# schematic.net
KiCad netlist of a schematic drawn in EAGLE
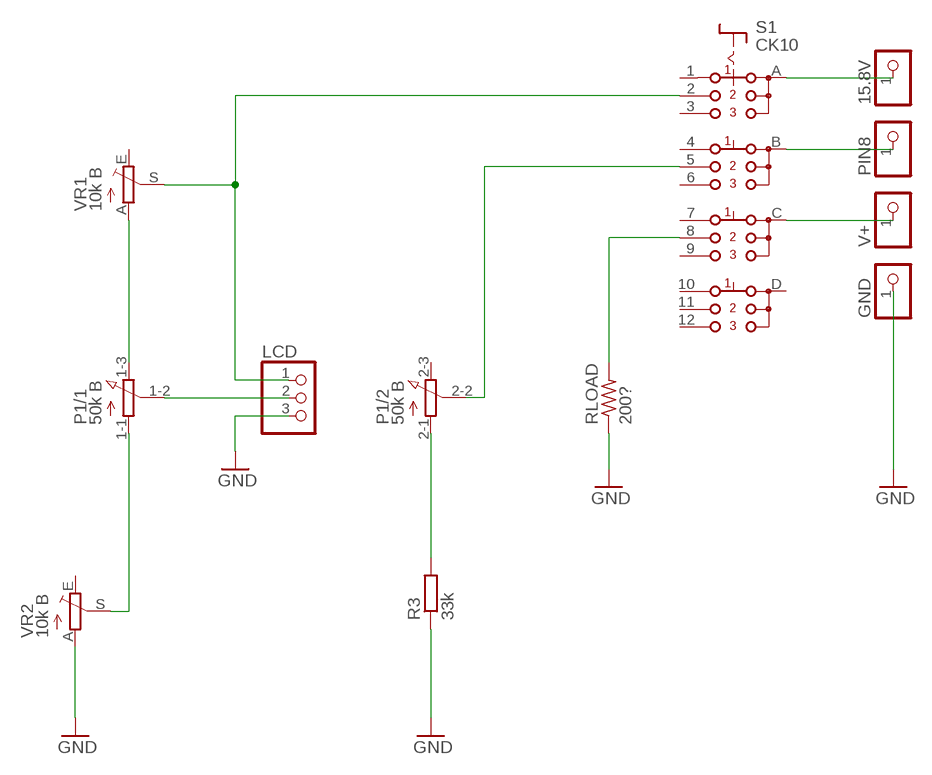
[diagram p0: schematic, sheet 1]

(export (version "E")
  (design (tool "Eeschema 10.0.6"))
  (components
    (comp (ref "15.8V")
      (value "PINHD-1X1")
      (footprint "eagle-import:1X01")
      (libsource (lib "eagle-import") (part "PINHD-1X1"))
    )
    (comp (ref "GND")
      (value "PINHD-1X1")
      (footprint "eagle-import:1X01")
      (libsource (lib "eagle-import") (part "PINHD-1X1"))
    )
    (comp (ref "LCD")
      (value "PINHD-1X3")
      (footprint "eagle-import:1X03")
      (libsource (lib "eagle-import") (part "PINHD-1X3"))
    )
    (comp (ref "P1")
      (value "50k B")
      (footprint "eagle-import:3RP_1610G")
      (libsource (lib "eagle-import") (part "3RP/1610G"))
    )
    (comp (ref "PIN8")
      (value "PINHD-1X1")
      (footprint "eagle-import:1X01")
      (libsource (lib "eagle-import") (part "PINHD-1X1"))
    )
    (comp (ref "R3")
      (value "33k")
      (footprint "eagle-import:0204_5")
      (libsource (lib "eagle-import") (part "R-EU_0204/5"))
    )
    (comp (ref "RLOAD")
      (value "200?")
      (footprint "eagle-import:VTA52")
      (libsource (lib "eagle-import") (part "R-US_VTA52"))
    )
    (comp (ref "S1")
      (value "CK10")
      (footprint "eagle-import:CK10")
      (libsource (lib "eagle-import") (part "CK10"))
    )
    (comp (ref "V+")
      (value "PINHD-1X1")
      (footprint "eagle-import:1X01")
      (libsource (lib "eagle-import") (part "PINHD-1X1"))
    )
    (comp (ref "VR1")
      (value "10k B")
      (footprint "eagle-import:RJ9W")
      (libsource (lib "eagle-import") (part "TRIM_EU-RJ9W"))
    )
    (comp (ref "VR2")
      (value "10k B")
      (footprint "eagle-import:RJ9W")
      (libsource (lib "eagle-import") (part "TRIM_EU-RJ9W"))
    )
  )
  (nets
    (net (code "1") (name "GND") (class "Default")
      (node (ref "GND") (pin "1") (pinfunction "1_1") (pintype "passive"))
      (node (ref "LCD") (pin "3") (pinfunction "3_3") (pintype "passive"))
      (node (ref "R3") (pin "1") (pinfunction "1_1") (pintype "passive"))
      (node (ref "RLOAD") (pin "1") (pinfunction "1_1") (pintype "passive"))
      (node (ref "VR2") (pin "A") (pinfunction "A_A") (pintype "passive"))
    )
    (net (code "2") (name "Net-(15.8V-Pad1)") (class "Default")
      (node (ref "15.8V") (pin "1") (pinfunction "1_1") (pintype "passive"))
      (node (ref "S1") (pin "A") (pinfunction "A_A") (pintype "passive"))
    )
    (net (code "3") (name "Net-(P1A-A)") (class "Default")
      (node (ref "P1") (pin "1-1") (pinfunction "A_1-1") (pintype "passive"))
      (node (ref "VR2") (pin "S") (pinfunction "S_S") (pintype "passive"))
    )
    (net (code "4") (name "Net-(P1A-E)") (class "Default")
      (node (ref "P1") (pin "1-3") (pinfunction "E_1-3") (pintype "passive"))
      (node (ref "VR1") (pin "A") (pinfunction "A_A") (pintype "passive"))
    )
    (net (code "5") (name "Net-(P1A-S)") (class "Default")
      (node (ref "LCD") (pin "2") (pinfunction "2_2") (pintype "passive"))
      (node (ref "P1") (pin "1-2") (pinfunction "S_1-2") (pintype "passive"))
    )
    (net (code "6") (name "Net-(P1B-A)") (class "Default")
      (node (ref "P1") (pin "2-1") (pinfunction "A_2-1") (pintype "passive"))
      (node (ref "R3") (pin "2") (pinfunction "2_2") (pintype "passive"))
    )
    (net (code "7") (name "Net-(P1B-S)") (class "Default")
      (node (ref "P1") (pin "2-2") (pinfunction "S_2-2") (pintype "passive"))
      (node (ref "S1") (pin "5") (pinfunction "B2_5") (pintype "passive"))
    )
    (net (code "8") (name "Net-(PIN8-Pad1)") (class "Default")
      (node (ref "PIN8") (pin "1") (pinfunction "1_1") (pintype "passive"))
      (node (ref "S1") (pin "B") (pinfunction "B_B") (pintype "passive"))
    )
    (net (code "9") (name "Net-(S1-A2)") (class "Default")
      (node (ref "LCD") (pin "1") (pinfunction "1_1") (pintype "passive"))
      (node (ref "S1") (pin "2") (pinfunction "A2_2") (pintype "passive"))
      (node (ref "VR1") (pin "S") (pinfunction "S_S") (pintype "passive"))
    )
    (net (code "10") (name "Net-(S1-C2)") (class "Default")
      (node (ref "RLOAD") (pin "2") (pinfunction "2_2") (pintype "passive"))
      (node (ref "S1") (pin "8") (pinfunction "C2_8") (pintype "passive"))
    )
    (net (code "11") (name "Net-(S1-PadC)") (class "Default")
      (node (ref "S1") (pin "C") (pinfunction "C_C") (pintype "passive"))
      (node (ref "V+") (pin "1") (pinfunction "1_1") (pintype "passive"))
    )
    (net (code "12") (name "unconnected-(P1B-E-Pad2-3)") (class "Default")
      (node (ref "P1") (pin "2-3") (pinfunction "E_2-3") (pintype "passive"))
    )
    (net (code "13") (name "unconnected-(S1-A1-Pad1)") (class "Default")
      (node (ref "S1") (pin "1") (pinfunction "A1_1") (pintype "passive"))
    )
    (net (code "14") (name "unconnected-(S1-A3-Pad3)") (class "Default")
      (node (ref "S1") (pin "3") (pinfunction "A3_3") (pintype "passive"))
    )
    (net (code "15") (name "unconnected-(S1-B1-Pad4)") (class "Default")
      (node (ref "S1") (pin "4") (pinfunction "B1_4") (pintype "passive"))
    )
    (net (code "16") (name "unconnected-(S1-B3-Pad6)") (class "Default")
      (node (ref "S1") (pin "6") (pinfunction "B3_6") (pintype "passive"))
    )
    (net (code "17") (name "unconnected-(S1-C1-Pad7)") (class "Default")
      (node (ref "S1") (pin "7") (pinfunction "C1_7") (pintype "passive"))
    )
    (net (code "18") (name "unconnected-(S1-C3-Pad9)") (class "Default")
      (node (ref "S1") (pin "9") (pinfunction "C3_9") (pintype "passive"))
    )
    (net (code "19") (name "unconnected-(S1-D1-Pad10)") (class "Default")
      (node (ref "S1") (pin "10") (pinfunction "D1_10") (pintype "passive"))
    )
    (net (code "20") (name "unconnected-(S1-D2-Pad11)") (class "Default")
      (node (ref "S1") (pin "11") (pinfunction "D2_11") (pintype "passive"))
    )
    (net (code "21") (name "unconnected-(S1-D3-Pad12)") (class "Default")
      (node (ref "S1") (pin "12") (pinfunction "D3_12") (pintype "passive"))
    )
    (net (code "22") (name "unconnected-(S1-PadD)") (class "Default")
      (node (ref "S1") (pin "D") (pinfunction "D_D") (pintype "passive"))
    )
    (net (code "23") (name "unconnected-(VR1-PadE)") (class "Default")
      (node (ref "VR1") (pin "E") (pinfunction "E_E") (pintype "passive"))
    )
    (net (code "24") (name "unconnected-(VR2-PadE)") (class "Default")
      (node (ref "VR2") (pin "E") (pinfunction "E_E") (pintype "passive"))
    )
  )
)
